# extension_board.net
KiCad netlist of a schematic drawn in EAGLE
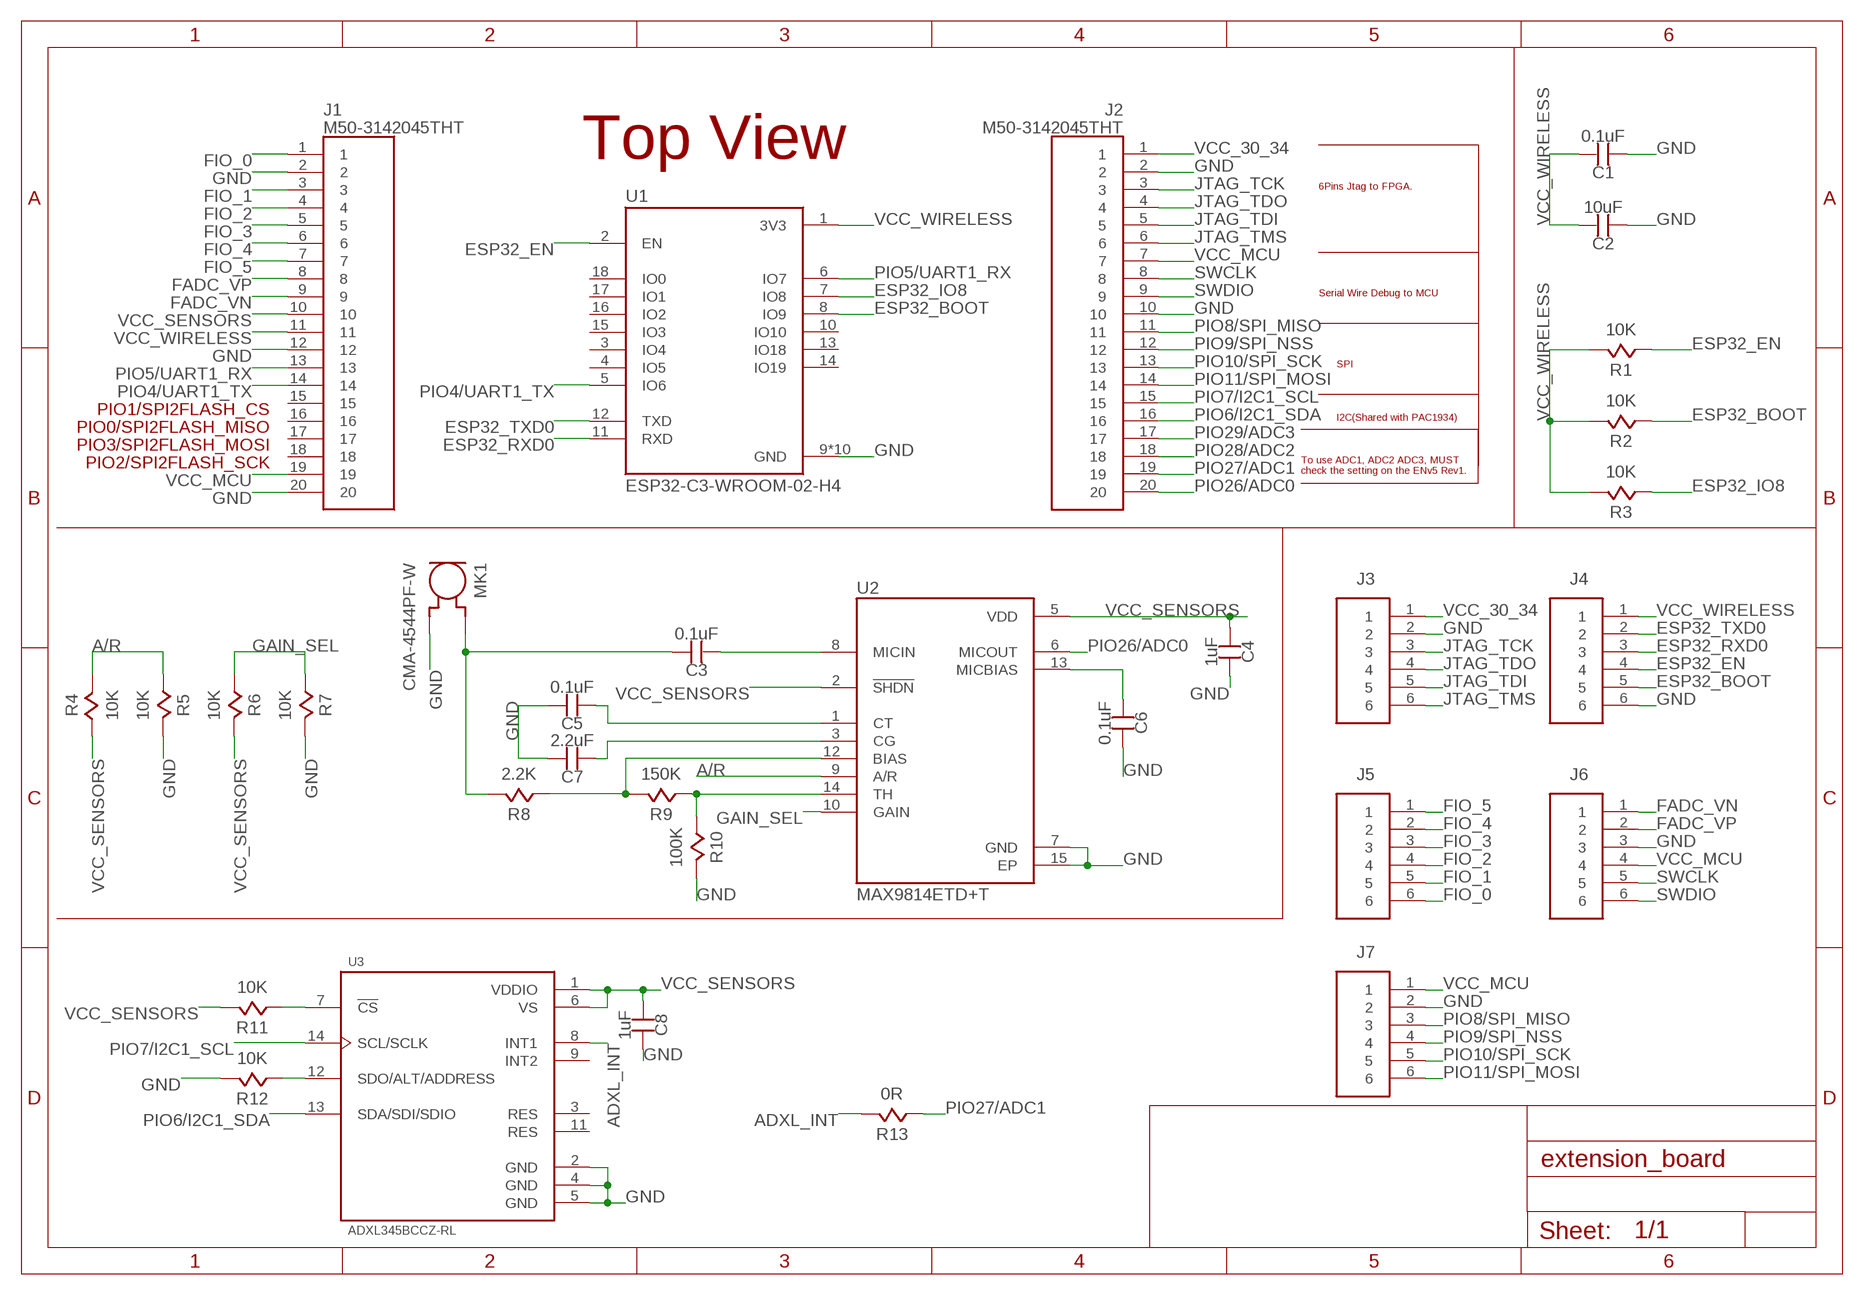
[diagram p0: schematic, sheet 1]

(export (version "E")
  (design (tool "Eeschema 10.0.6"))
  (components
    (comp (ref "C1")
      (value "0.1uF")
      (footprint "eagle-import:0402")
      (libsource (lib "eagle-import") (part "CAPACITOR0402"))
    )
    (comp (ref "C2")
      (value "10uF")
      (footprint "eagle-import:0805")
      (libsource (lib "eagle-import") (part "CAPACITOR0805"))
    )
    (comp (ref "C3")
      (value "0.1uF")
      (footprint "eagle-import:0402")
      (libsource (lib "eagle-import") (part "CAPACITOR0402"))
    )
    (comp (ref "C4")
      (value "1uF")
      (footprint "eagle-import:0402")
      (libsource (lib "eagle-import") (part "CAPACITOR0402"))
    )
    (comp (ref "C5")
      (value "0.1uF")
      (footprint "eagle-import:0402")
      (libsource (lib "eagle-import") (part "CAPACITOR0402"))
    )
    (comp (ref "C6")
      (value "0.1uF")
      (footprint "eagle-import:0402")
      (libsource (lib "eagle-import") (part "CAPACITOR0402"))
    )
    (comp (ref "C7")
      (value "2.2uF")
      (footprint "eagle-import:0402")
      (libsource (lib "eagle-import") (part "CAPACITOR0402"))
    )
    (comp (ref "C8")
      (value "1uF")
      (footprint "eagle-import:0402")
      (libsource (lib "eagle-import") (part "CAPACITOR0402"))
    )
    (comp (ref "J1")
      (value "M50-3142045THT")
      (footprint "eagle-import:20X1_HEADER_THT_1.27MM")
      (libsource (lib "eagle-import") (part "M50-3142045THT"))
    )
    (comp (ref "J2")
      (value "M50-3142045THT")
      (footprint "eagle-import:20X1_HEADER_THT_1.27MM")
      (libsource (lib "eagle-import") (part "M50-3142045THT"))
    )
    (comp (ref "J3")
      (value "MALE_HEADER_6X1_2.54MM")
      (footprint "eagle-import:HDR_6X1_2.54MM")
      (libsource (lib "eagle-import") (part "MALE_HEADER_6X1_2.54MM"))
    )
    (comp (ref "J4")
      (value "MALE_HEADER_6X1_2.54MM")
      (footprint "eagle-import:HDR_6X1_2.54MM")
      (libsource (lib "eagle-import") (part "MALE_HEADER_6X1_2.54MM"))
    )
    (comp (ref "J5")
      (value "MALE_HEADER_6X1_2.54MM")
      (footprint "eagle-import:HDR_6X1_2.54MM")
      (libsource (lib "eagle-import") (part "MALE_HEADER_6X1_2.54MM"))
    )
    (comp (ref "J6")
      (value "MALE_HEADER_6X1_2.54MM")
      (footprint "eagle-import:HDR_6X1_2.54MM")
      (libsource (lib "eagle-import") (part "MALE_HEADER_6X1_2.54MM"))
    )
    (comp (ref "J7")
      (value "MALE_HEADER_6X1_2.54MM")
      (footprint "eagle-import:HDR_6X1_2.54MM")
      (libsource (lib "eagle-import") (part "MALE_HEADER_6X1_2.54MM"))
    )
    (comp (ref "MK1")
      (value "CMA-4544PF-W")
      (footprint "eagle-import:MIC_CMA-4544PF-W")
      (fields (field (name "MF") "CUI Devices"))
      (libsource (lib "eagle-import") (part "CMA-4544PF-W"))
    )
    (comp (ref "R1")
      (value "10K")
      (footprint "eagle-import:0402")
      (libsource (lib "eagle-import") (part "RESISTORSMD_0402"))
    )
    (comp (ref "R2")
      (value "10K")
      (footprint "eagle-import:0402")
      (libsource (lib "eagle-import") (part "RESISTORSMD_0402"))
    )
    (comp (ref "R3")
      (value "10K")
      (footprint "eagle-import:0402")
      (libsource (lib "eagle-import") (part "RESISTORSMD_0402"))
    )
    (comp (ref "R4")
      (value "10K")
      (footprint "eagle-import:0402")
      (libsource (lib "eagle-import") (part "RESISTORSMD_0402"))
    )
    (comp (ref "R5")
      (value "10K")
      (footprint "eagle-import:0402")
      (libsource (lib "eagle-import") (part "RESISTORSMD_0402"))
    )
    (comp (ref "R6")
      (value "10K")
      (footprint "eagle-import:0402")
      (libsource (lib "eagle-import") (part "RESISTORSMD_0402"))
    )
    (comp (ref "R7")
      (value "10K")
      (footprint "eagle-import:0402")
      (libsource (lib "eagle-import") (part "RESISTORSMD_0402"))
    )
    (comp (ref "R8")
      (value "2.2K")
      (footprint "eagle-import:0402")
      (libsource (lib "eagle-import") (part "RESISTORSMD_0402"))
    )
    (comp (ref "R9")
      (value "150K")
      (footprint "eagle-import:0402")
      (libsource (lib "eagle-import") (part "RESISTORSMD_0402"))
    )
    (comp (ref "R10")
      (value "100K")
      (footprint "eagle-import:0402")
      (libsource (lib "eagle-import") (part "RESISTORSMD_0402"))
    )
    (comp (ref "R11")
      (value "10K")
      (footprint "eagle-import:0402")
      (libsource (lib "eagle-import") (part "RESISTORSMD_0402"))
    )
    (comp (ref "R12")
      (value "10K")
      (footprint "eagle-import:0402")
      (libsource (lib "eagle-import") (part "RESISTORSMD_0402"))
    )
    (comp (ref "R13")
      (value "0R")
      (footprint "eagle-import:0402")
      (libsource (lib "eagle-import") (part "RESISTORSMD_0402"))
    )
    (comp (ref "U1")
      (value "ESP32-C3-WROOM-02-H4")
      (footprint "eagle-import:MODULE_ESP32-C3-WROOM-02-H4")
      (fields (field (name "MANUFACTURER") "Espressif"))
      (libsource (lib "eagle-import") (part "ESP32-C3-WROOM-02-H4"))
    )
    (comp (ref "U2")
      (value "MAX9814ETD+T")
      (footprint "eagle-import:SON40P300X300X80-15N")
      (fields (field (name "MF") "Maxim Integrated") (field (name "MP") "MAX9814ETD+"))
      (libsource (lib "eagle-import") (part "MAX9814ETD+T"))
    )
    (comp (ref "U3")
      (value "ADXL345BCCZ-RL")
      (footprint "eagle-import:PQFN80P300X500X79-14N")
      (fields (field (name "MF") "Analog Devices Inc."))
      (libsource (lib "eagle-import") (part "ADXL345BCCZ-RL"))
    )
  )
  (nets
    (net (code "1") (name "/ADXL_INT") (class "Default")
      (node (ref "R13") (pin "2") (pinfunction "2_2") (pintype "bidirectional"))
      (node (ref "U3") (pin "8") (pinfunction "INT1_8") (pintype "bidirectional"))
    )
    (net (code "2") (name "/A{slash}R") (class "Default")
      (node (ref "R4") (pin "2") (pinfunction "2_2") (pintype "bidirectional"))
      (node (ref "R5") (pin "1") (pinfunction "1_1") (pintype "bidirectional"))
      (node (ref "U2") (pin "9") (pinfunction "A/R_9") (pintype "passive"))
    )
    (net (code "3") (name "/ESP32_BOOT") (class "Default")
      (node (ref "J4") (pin "5") (pinfunction "5_5") (pintype "bidirectional"))
      (node (ref "R2") (pin "1") (pinfunction "1_1") (pintype "bidirectional"))
      (node (ref "U1") (pin "8") (pinfunction "IO9_8") (pintype "bidirectional"))
    )
    (net (code "4") (name "/ESP32_EN") (class "Default")
      (node (ref "J4") (pin "4") (pinfunction "4_4") (pintype "bidirectional"))
      (node (ref "R1") (pin "1") (pinfunction "1_1") (pintype "bidirectional"))
      (node (ref "U1") (pin "2") (pinfunction "EN_2") (pintype "input"))
    )
    (net (code "5") (name "/ESP32_IO8") (class "Default")
      (node (ref "R3") (pin "1") (pinfunction "1_1") (pintype "bidirectional"))
      (node (ref "U1") (pin "7") (pinfunction "IO8_7") (pintype "bidirectional"))
    )
    (net (code "6") (name "/ESP32_RXD0") (class "Default")
      (node (ref "J4") (pin "3") (pinfunction "3_3") (pintype "bidirectional"))
      (node (ref "U1") (pin "11") (pinfunction "RXD_11") (pintype "bidirectional"))
    )
    (net (code "7") (name "/ESP32_TXD0") (class "Default")
      (node (ref "J4") (pin "2") (pinfunction "2_2") (pintype "bidirectional"))
      (node (ref "U1") (pin "12") (pinfunction "TXD_12") (pintype "bidirectional"))
    )
    (net (code "8") (name "/FADC_VN") (class "Default")
      (node (ref "J1") (pin "9") (pinfunction "9_9") (pintype "bidirectional"))
      (node (ref "J6") (pin "1") (pinfunction "1_1") (pintype "bidirectional"))
    )
    (net (code "9") (name "/FADC_VP") (class "Default")
      (node (ref "J1") (pin "8") (pinfunction "8_8") (pintype "bidirectional"))
      (node (ref "J6") (pin "2") (pinfunction "2_2") (pintype "bidirectional"))
    )
    (net (code "10") (name "/FIO_0") (class "Default")
      (node (ref "J1") (pin "1") (pinfunction "1_1") (pintype "bidirectional"))
      (node (ref "J5") (pin "6") (pinfunction "6_6") (pintype "bidirectional"))
    )
    (net (code "11") (name "/FIO_1") (class "Default")
      (node (ref "J1") (pin "3") (pinfunction "3_3") (pintype "bidirectional"))
      (node (ref "J5") (pin "5") (pinfunction "5_5") (pintype "bidirectional"))
    )
    (net (code "12") (name "/FIO_2") (class "Default")
      (node (ref "J1") (pin "4") (pinfunction "4_4") (pintype "bidirectional"))
      (node (ref "J5") (pin "4") (pinfunction "4_4") (pintype "bidirectional"))
    )
    (net (code "13") (name "/FIO_3") (class "Default")
      (node (ref "J1") (pin "5") (pinfunction "5_5") (pintype "bidirectional"))
      (node (ref "J5") (pin "3") (pinfunction "3_3") (pintype "bidirectional"))
    )
    (net (code "14") (name "/FIO_4") (class "Default")
      (node (ref "J1") (pin "6") (pinfunction "6_6") (pintype "bidirectional"))
      (node (ref "J5") (pin "2") (pinfunction "2_2") (pintype "bidirectional"))
    )
    (net (code "15") (name "/FIO_5") (class "Default")
      (node (ref "J1") (pin "7") (pinfunction "7_7") (pintype "bidirectional"))
      (node (ref "J5") (pin "1") (pinfunction "1_1") (pintype "bidirectional"))
    )
    (net (code "16") (name "/GAIN_SEL") (class "Default")
      (node (ref "R6") (pin "1") (pinfunction "1_1") (pintype "bidirectional"))
      (node (ref "R7") (pin "1") (pinfunction "1_1") (pintype "bidirectional"))
      (node (ref "U2") (pin "10") (pinfunction "GAIN_10") (pintype "passive"))
    )
    (net (code "17") (name "/GND") (class "Default")
      (node (ref "C1") (pin "1") (pinfunction "P$1_1") (pintype "bidirectional"))
      (node (ref "C2") (pin "1") (pinfunction "P$1_1") (pintype "bidirectional"))
      (node (ref "C4") (pin "2") (pinfunction "P$2_2") (pintype "bidirectional"))
      (node (ref "C5") (pin "2") (pinfunction "P$2_2") (pintype "bidirectional"))
      (node (ref "C6") (pin "2") (pinfunction "P$2_2") (pintype "bidirectional"))
      (node (ref "C7") (pin "2") (pinfunction "P$2_2") (pintype "bidirectional"))
      (node (ref "C8") (pin "2") (pinfunction "P$2_2") (pintype "bidirectional"))
      (node (ref "J1") (pin "12") (pinfunction "12_12") (pintype "bidirectional"))
      (node (ref "J1") (pin "2") (pinfunction "2_2") (pintype "bidirectional"))
      (node (ref "J1") (pin "20") (pinfunction "20_20") (pintype "bidirectional"))
      (node (ref "J2") (pin "10") (pinfunction "10_10") (pintype "bidirectional"))
      (node (ref "J2") (pin "2") (pinfunction "2_2") (pintype "bidirectional"))
      (node (ref "J3") (pin "2") (pinfunction "2_2") (pintype "bidirectional"))
      (node (ref "J4") (pin "6") (pinfunction "6_6") (pintype "bidirectional"))
      (node (ref "J6") (pin "3") (pinfunction "3_3") (pintype "bidirectional"))
      (node (ref "J7") (pin "2") (pinfunction "2_2") (pintype "bidirectional"))
      (node (ref "MK1") (pin "2") (pinfunction "GND_2") (pintype "power_in"))
      (node (ref "R10") (pin "2") (pinfunction "2_2") (pintype "bidirectional"))
      (node (ref "R12") (pin "2") (pinfunction "2_2") (pintype "bidirectional"))
      (node (ref "R5") (pin "2") (pinfunction "2_2") (pintype "bidirectional"))
      (node (ref "R7") (pin "2") (pinfunction "2_2") (pintype "bidirectional"))
      (node (ref "U1") (pin "19") (pinfunction "GND_19") (pintype "power_in"))
      (node (ref "U1") (pin "20") (pinfunction "GND_20") (pintype "power_in"))
      (node (ref "U1") (pin "21") (pinfunction "GND_21") (pintype "power_in"))
      (node (ref "U1") (pin "22") (pinfunction "GND_22") (pintype "power_in"))
      (node (ref "U1") (pin "23") (pinfunction "GND_23") (pintype "power_in"))
      (node (ref "U1") (pin "24") (pinfunction "GND_24") (pintype "power_in"))
      (node (ref "U1") (pin "25") (pinfunction "GND_25") (pintype "power_in"))
      (node (ref "U1") (pin "26") (pinfunction "GND_26") (pintype "power_in"))
      (node (ref "U1") (pin "27") (pinfunction "GND_27") (pintype "power_in"))
      (node (ref "U1") (pin "9") (pinfunction "GND_9") (pintype "power_in"))
      (node (ref "U2") (pin "15") (pinfunction "EP_15") (pintype "bidirectional"))
      (node (ref "U2") (pin "7") (pinfunction "GND_7") (pintype "bidirectional"))
      (node (ref "U3") (pin "2") (pinfunction "GND_2") (pintype "bidirectional"))
      (node (ref "U3") (pin "4") (pinfunction "GND_4") (pintype "bidirectional"))
      (node (ref "U3") (pin "5") (pinfunction "GND_5") (pintype "bidirectional"))
    )
    (net (code "18") (name "/JTAG_TCK") (class "Default")
      (node (ref "J2") (pin "3") (pinfunction "3_3") (pintype "bidirectional"))
      (node (ref "J3") (pin "3") (pinfunction "3_3") (pintype "bidirectional"))
    )
    (net (code "19") (name "/JTAG_TDI") (class "Default")
      (node (ref "J2") (pin "5") (pinfunction "5_5") (pintype "bidirectional"))
      (node (ref "J3") (pin "5") (pinfunction "5_5") (pintype "bidirectional"))
    )
    (net (code "20") (name "/JTAG_TDO") (class "Default")
      (node (ref "J2") (pin "4") (pinfunction "4_4") (pintype "bidirectional"))
      (node (ref "J3") (pin "4") (pinfunction "4_4") (pintype "bidirectional"))
    )
    (net (code "21") (name "/JTAG_TMS") (class "Default")
      (node (ref "J2") (pin "6") (pinfunction "6_6") (pintype "bidirectional"))
      (node (ref "J3") (pin "6") (pinfunction "6_6") (pintype "bidirectional"))
    )
    (net (code "22") (name "/PIO4{slash}UART1_TX") (class "Default")
      (node (ref "J1") (pin "14") (pinfunction "14_14") (pintype "bidirectional"))
      (node (ref "U1") (pin "5") (pinfunction "IO6_5") (pintype "bidirectional"))
    )
    (net (code "23") (name "/PIO5{slash}UART1_RX") (class "Default")
      (node (ref "J1") (pin "13") (pinfunction "13_13") (pintype "bidirectional"))
      (node (ref "U1") (pin "6") (pinfunction "IO7_6") (pintype "bidirectional"))
    )
    (net (code "24") (name "/PIO6{slash}I2C1_SDA") (class "Default")
      (node (ref "J2") (pin "16") (pinfunction "16_16") (pintype "bidirectional"))
      (node (ref "U3") (pin "13") (pinfunction "SDA/SDI/SDIO_13") (pintype "bidirectional"))
    )
    (net (code "25") (name "/PIO7{slash}I2C1_SCL") (class "Default")
      (node (ref "J2") (pin "15") (pinfunction "15_15") (pintype "bidirectional"))
      (node (ref "U3") (pin "14") (pinfunction "SCL/SCLK_14") (pintype "bidirectional"))
    )
    (net (code "26") (name "/PIO8{slash}SPI_MISO") (class "Default")
      (node (ref "J2") (pin "11") (pinfunction "11_11") (pintype "bidirectional"))
      (node (ref "J7") (pin "3") (pinfunction "3_3") (pintype "bidirectional"))
    )
    (net (code "27") (name "/PIO9{slash}SPI_NSS") (class "Default")
      (node (ref "J2") (pin "12") (pinfunction "12_12") (pintype "bidirectional"))
      (node (ref "J7") (pin "4") (pinfunction "4_4") (pintype "bidirectional"))
    )
    (net (code "28") (name "/PIO10{slash}SPI_SCK") (class "Default")
      (node (ref "J2") (pin "13") (pinfunction "13_13") (pintype "bidirectional"))
      (node (ref "J7") (pin "5") (pinfunction "5_5") (pintype "bidirectional"))
    )
    (net (code "29") (name "/PIO11{slash}SPI_MOSI") (class "Default")
      (node (ref "J2") (pin "14") (pinfunction "14_14") (pintype "bidirectional"))
      (node (ref "J7") (pin "6") (pinfunction "6_6") (pintype "bidirectional"))
    )
    (net (code "30") (name "/PIO26{slash}ADC0") (class "Default")
      (node (ref "J2") (pin "20") (pinfunction "20_20") (pintype "bidirectional"))
      (node (ref "U2") (pin "6") (pinfunction "MICOUT_6") (pintype "output"))
    )
    (net (code "31") (name "/PIO27{slash}ADC1") (class "Default")
      (node (ref "J2") (pin "19") (pinfunction "19_19") (pintype "bidirectional"))
      (node (ref "R13") (pin "1") (pinfunction "1_1") (pintype "bidirectional"))
    )
    (net (code "32") (name "/PIO28{slash}ADC2") (class "Default")
      (node (ref "J2") (pin "18") (pinfunction "18_18") (pintype "bidirectional"))
    )
    (net (code "33") (name "/PIO29{slash}ADC3") (class "Default")
      (node (ref "J2") (pin "17") (pinfunction "17_17") (pintype "bidirectional"))
    )
    (net (code "34") (name "/SWCLK") (class "Default")
      (node (ref "J2") (pin "8") (pinfunction "8_8") (pintype "bidirectional"))
      (node (ref "J6") (pin "5") (pinfunction "5_5") (pintype "bidirectional"))
    )
    (net (code "35") (name "/SWDIO") (class "Default")
      (node (ref "J2") (pin "9") (pinfunction "9_9") (pintype "bidirectional"))
      (node (ref "J6") (pin "6") (pinfunction "6_6") (pintype "bidirectional"))
    )
    (net (code "36") (name "/VCC_30_34") (class "Default")
      (node (ref "J2") (pin "1") (pinfunction "1_1") (pintype "bidirectional"))
      (node (ref "J3") (pin "1") (pinfunction "1_1") (pintype "bidirectional"))
    )
    (net (code "37") (name "/VCC_MCU") (class "Default")
      (node (ref "J1") (pin "19") (pinfunction "19_19") (pintype "bidirectional"))
      (node (ref "J2") (pin "7") (pinfunction "7_7") (pintype "bidirectional"))
      (node (ref "J6") (pin "4") (pinfunction "4_4") (pintype "bidirectional"))
      (node (ref "J7") (pin "1") (pinfunction "1_1") (pintype "bidirectional"))
    )
    (net (code "38") (name "/VCC_SENSORS") (class "Default")
      (node (ref "C4") (pin "1") (pinfunction "P$1_1") (pintype "bidirectional"))
      (node (ref "C8") (pin "1") (pinfunction "P$1_1") (pintype "bidirectional"))
      (node (ref "J1") (pin "10") (pinfunction "10_10") (pintype "bidirectional"))
      (node (ref "R11") (pin "2") (pinfunction "2_2") (pintype "bidirectional"))
      (node (ref "R4") (pin "1") (pinfunction "1_1") (pintype "bidirectional"))
      (node (ref "R6") (pin "2") (pinfunction "2_2") (pintype "bidirectional"))
      (node (ref "U2") (pin "2") (pinfunction "~{SHDN}_2") (pintype "input"))
      (node (ref "U2") (pin "5") (pinfunction "VDD_5") (pintype "bidirectional"))
      (node (ref "U3") (pin "1") (pinfunction "VDDIO_1") (pintype "bidirectional"))
      (node (ref "U3") (pin "6") (pinfunction "VS_6") (pintype "bidirectional"))
    )
    (net (code "39") (name "/VCC_WIRELESS") (class "Default")
      (node (ref "C1") (pin "2") (pinfunction "P$2_2") (pintype "bidirectional"))
      (node (ref "C2") (pin "2") (pinfunction "P$2_2") (pintype "bidirectional"))
      (node (ref "J1") (pin "11") (pinfunction "11_11") (pintype "bidirectional"))
      (node (ref "J4") (pin "1") (pinfunction "1_1") (pintype "bidirectional"))
      (node (ref "R1") (pin "2") (pinfunction "2_2") (pintype "bidirectional"))
      (node (ref "R2") (pin "2") (pinfunction "2_2") (pintype "bidirectional"))
      (node (ref "R3") (pin "2") (pinfunction "2_2") (pintype "bidirectional"))
      (node (ref "U1") (pin "1") (pinfunction "3V3_1") (pintype "power_in"))
    )
    (net (code "40") (name "Net-(C3-P$1)") (class "Default")
      (node (ref "C3") (pin "1") (pinfunction "P$1_1") (pintype "bidirectional"))
      (node (ref "U2") (pin "8") (pinfunction "MICIN_8") (pintype "input"))
    )
    (net (code "41") (name "Net-(C3-P$2)") (class "Default")
      (node (ref "C3") (pin "2") (pinfunction "P$2_2") (pintype "bidirectional"))
      (node (ref "MK1") (pin "1") (pinfunction "OUT_1") (pintype "output"))
      (node (ref "R8") (pin "2") (pinfunction "2_2") (pintype "bidirectional"))
    )
    (net (code "42") (name "Net-(C5-P$1)") (class "Default")
      (node (ref "C5") (pin "1") (pinfunction "P$1_1") (pintype "bidirectional"))
      (node (ref "U2") (pin "1") (pinfunction "CT_1") (pintype "passive"))
    )
    (net (code "43") (name "Net-(C6-P$1)") (class "Default")
      (node (ref "C6") (pin "1") (pinfunction "P$1_1") (pintype "bidirectional"))
      (node (ref "U2") (pin "13") (pinfunction "MICBIAS_13") (pintype "output"))
    )
    (net (code "44") (name "Net-(C7-P$1)") (class "Default")
      (node (ref "C7") (pin "1") (pinfunction "P$1_1") (pintype "bidirectional"))
      (node (ref "U2") (pin "3") (pinfunction "CG_3") (pintype "passive"))
    )
    (net (code "45") (name "Net-(U2-BIAS)") (class "Default")
      (node (ref "R8") (pin "1") (pinfunction "1_1") (pintype "bidirectional"))
      (node (ref "R9") (pin "2") (pinfunction "2_2") (pintype "bidirectional"))
      (node (ref "U2") (pin "12") (pinfunction "BIAS_12") (pintype "passive"))
    )
    (net (code "46") (name "Net-(U2-TH)") (class "Default")
      (node (ref "R10") (pin "1") (pinfunction "1_1") (pintype "bidirectional"))
      (node (ref "R9") (pin "1") (pinfunction "1_1") (pintype "bidirectional"))
      (node (ref "U2") (pin "14") (pinfunction "TH_14") (pintype "passive"))
    )
    (net (code "47") (name "Net-(U3-SDO{slash}ALT{slash}ADDRESS)") (class "Default")
      (node (ref "R12") (pin "1") (pinfunction "1_1") (pintype "bidirectional"))
      (node (ref "U3") (pin "12") (pinfunction "SDO/ALT/ADDRESS_12") (pintype "bidirectional"))
    )
    (net (code "48") (name "Net-(U3-~{CS})") (class "Default")
      (node (ref "R11") (pin "1") (pinfunction "1_1") (pintype "bidirectional"))
      (node (ref "U3") (pin "7") (pinfunction "~{CS}_7") (pintype "bidirectional"))
    )
    (net (code "49") (name "unconnected-(J1-Pad15)") (class "Default")
      (node (ref "J1") (pin "15") (pinfunction "15_15") (pintype "bidirectional"))
    )
    (net (code "50") (name "unconnected-(J1-Pad16)") (class "Default")
      (node (ref "J1") (pin "16") (pinfunction "16_16") (pintype "bidirectional"))
    )
    (net (code "51") (name "unconnected-(J1-Pad17)") (class "Default")
      (node (ref "J1") (pin "17") (pinfunction "17_17") (pintype "bidirectional"))
    )
    (net (code "52") (name "unconnected-(J1-Pad18)") (class "Default")
      (node (ref "J1") (pin "18") (pinfunction "18_18") (pintype "bidirectional"))
    )
    (net (code "53") (name "unconnected-(U1-IO0-Pad18)") (class "Default")
      (node (ref "U1") (pin "18") (pinfunction "IO0_18") (pintype "bidirectional"))
    )
    (net (code "54") (name "unconnected-(U1-IO1-Pad17)") (class "Default")
      (node (ref "U1") (pin "17") (pinfunction "IO1_17") (pintype "bidirectional"))
    )
    (net (code "55") (name "unconnected-(U1-IO2-Pad16)") (class "Default")
      (node (ref "U1") (pin "16") (pinfunction "IO2_16") (pintype "bidirectional"))
    )
    (net (code "56") (name "unconnected-(U1-IO3-Pad15)") (class "Default")
      (node (ref "U1") (pin "15") (pinfunction "IO3_15") (pintype "bidirectional"))
    )
    (net (code "57") (name "unconnected-(U1-IO4-Pad3)") (class "Default")
      (node (ref "U1") (pin "3") (pinfunction "IO4_3") (pintype "bidirectional"))
    )
    (net (code "58") (name "unconnected-(U1-IO5-Pad4)") (class "Default")
      (node (ref "U1") (pin "4") (pinfunction "IO5_4") (pintype "bidirectional"))
    )
    (net (code "59") (name "unconnected-(U1-IO10-Pad10)") (class "Default")
      (node (ref "U1") (pin "10") (pinfunction "IO10_10") (pintype "bidirectional"))
    )
    (net (code "60") (name "unconnected-(U1-IO18-Pad13)") (class "Default")
      (node (ref "U1") (pin "13") (pinfunction "IO18_13") (pintype "bidirectional"))
    )
    (net (code "61") (name "unconnected-(U1-IO19-Pad14)") (class "Default")
      (node (ref "U1") (pin "14") (pinfunction "IO19_14") (pintype "bidirectional"))
    )
    (net (code "62") (name "unconnected-(U3-INT2-Pad9)") (class "Default")
      (node (ref "U3") (pin "9") (pinfunction "INT2_9") (pintype "bidirectional"))
    )
    (net (code "63") (name "unconnected-(U3-RES-Pad3)") (class "Default")
      (node (ref "U3") (pin "3") (pinfunction "RES_3") (pintype "bidirectional"))
    )
    (net (code "64") (name "unconnected-(U3-RES-Pad11)") (class "Default")
      (node (ref "U3") (pin "11") (pinfunction "RES_11") (pintype "bidirectional"))
    )
  )
)
